# Sherlock.net
KiCad netlist of a schematic drawn in EAGLE
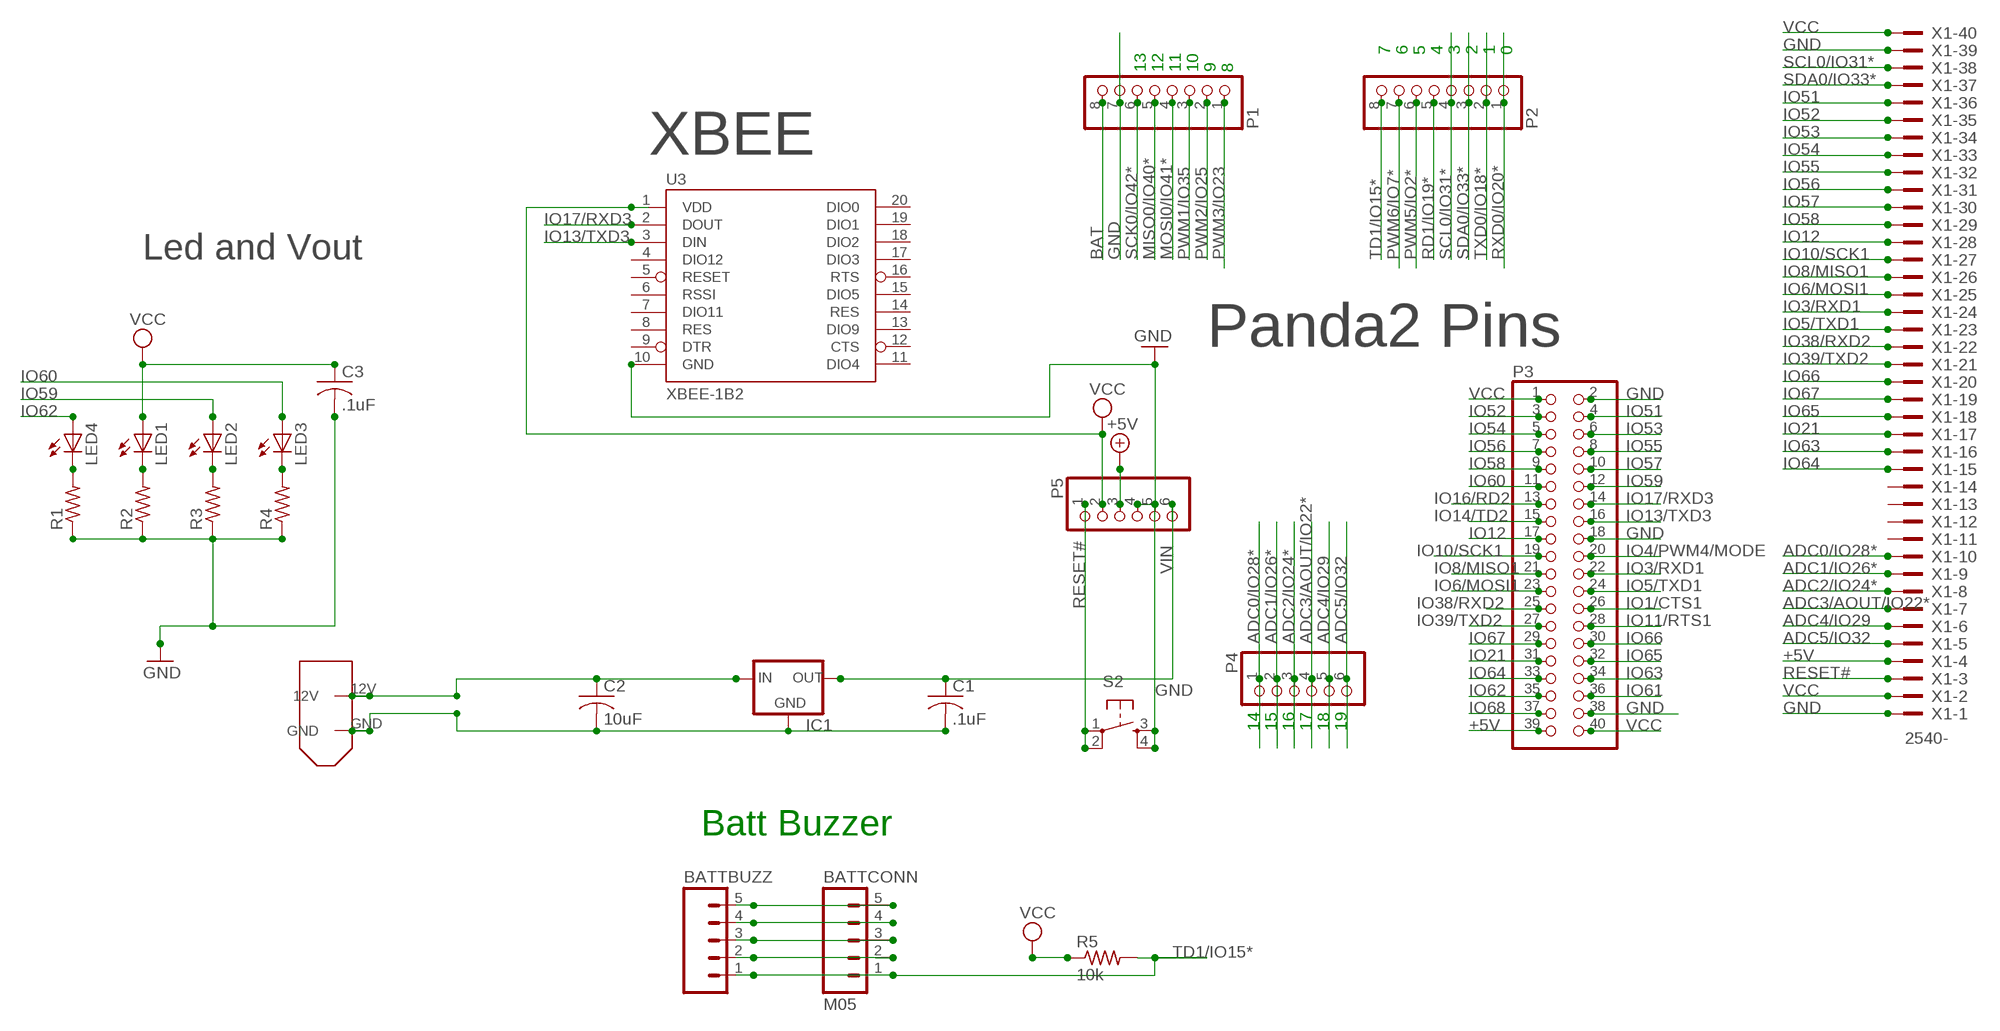
[diagram p0: schematic, sheet 1]

(export (version "E")
  (design (tool "Eeschema 10.0.6"))
  (components
    (comp (ref "BATTBUZZ")
      (value "M05PTH")
      (footprint "eagle-import:1X05")
      (libsource (lib "eagle-import") (part "M05PTH"))
    )
    (comp (ref "BATTCONN")
      (value "M05")
      (footprint "eagle-import:1X05")
      (libsource (lib "eagle-import") (part "M05"))
    )
    (comp (ref "C1")
      (value ".1uF")
      (footprint "eagle-import:C0603")
      (libsource (lib "eagle-import") (part "C-USC0603"))
    )
    (comp (ref "C2")
      (value "10uF")
      (footprint "eagle-import:C0603")
      (libsource (lib "eagle-import") (part "C-USC0603"))
    )
    (comp (ref "C3")
      (value ".1uF")
      (footprint "eagle-import:C0603K")
      (libsource (lib "eagle-import") (part "C-USC0603K"))
    )
    (comp (ref "IC1")
      (value "78XXL")
      (footprint "eagle-import:78XXL")
      (libsource (lib "eagle-import") (part "78XXL"))
    )
    (comp (ref "LED1")
      (value "LED0603")
      (footprint "eagle-import:LED-0603")
      (libsource (lib "eagle-import") (part "LED0603"))
    )
    (comp (ref "LED2")
      (value "LED0603")
      (footprint "eagle-import:LED-0603")
      (libsource (lib "eagle-import") (part "LED0603"))
    )
    (comp (ref "LED3")
      (value "LED0603")
      (footprint "eagle-import:LED-0603")
      (libsource (lib "eagle-import") (part "LED0603"))
    )
    (comp (ref "LED4")
      (value "LED0603")
      (footprint "eagle-import:LED-0603")
      (libsource (lib "eagle-import") (part "LED0603"))
    )
    (comp (ref "P1")
      (value "PINHD-1X08_2.54-S")
      (footprint "eagle-import:1X08-S")
      (libsource (lib "eagle-import") (part "PINHD-1X08_2.54-S"))
    )
    (comp (ref "P2")
      (value "PINHD-1X08_2.54-S")
      (footprint "eagle-import:1X08-S")
      (libsource (lib "eagle-import") (part "PINHD-1X08_2.54-S"))
    )
    (comp (ref "P3")
      (value "PINHD-2X20")
      (footprint "eagle-import:2X20")
      (libsource (lib "eagle-import") (part "PINHD-2X20"))
    )
    (comp (ref "P4")
      (value "PINHD-1X06_2.54-S")
      (footprint "eagle-import:1X06-S")
      (libsource (lib "eagle-import") (part "PINHD-1X06_2.54-S"))
    )
    (comp (ref "P5")
      (value "PINHD-1X06_2.54-S")
      (footprint "eagle-import:1X06-S")
      (libsource (lib "eagle-import") (part "PINHD-1X06_2.54-S"))
    )
    (comp (ref "R1")
      (value "R-US_R0603")
      (footprint "eagle-import:R0603")
      (libsource (lib "eagle-import") (part "R-US_R0603"))
    )
    (comp (ref "R2")
      (value "R-US_R0603")
      (footprint "eagle-import:R0603")
      (libsource (lib "eagle-import") (part "R-US_R0603"))
    )
    (comp (ref "R3")
      (value "R-US_R0603")
      (footprint "eagle-import:R0603")
      (libsource (lib "eagle-import") (part "R-US_R0603"))
    )
    (comp (ref "R4")
      (value "R-US_R0603")
      (footprint "eagle-import:R0603")
      (libsource (lib "eagle-import") (part "R-US_R0603"))
    )
    (comp (ref "R5")
      (value "10k")
      (footprint "eagle-import:R0603")
      (libsource (lib "eagle-import") (part "resistor_R-US_R0603"))
    )
    (comp (ref "S2")
      (value "TAC_SWITCHPTH")
      (footprint "eagle-import:TACTILE-PTH")
      (libsource (lib "eagle-import") (part "TAC_SWITCHPTH"))
    )
    (comp (ref "U$1")
      (value "XT60CONNECTOR")
      (footprint "eagle-import:XT60CONNECTOR")
      (libsource (lib "eagle-import") (part "XT60CONNECTOR"))
    )
    (comp (ref "U3")
      (value "XBEE-1B2")
      (footprint "eagle-import:XBEE-SILK")
      (libsource (lib "eagle-import") (part "XBEE-1B2"))
    )
    (comp (ref "X1")
      (value "2540-")
      (footprint "eagle-import:PAK100_2500-40")
      (fields (field (name "OC_FARNELL") "unknown"))
      (libsource (lib "eagle-import") (part "2540-"))
    )
  )
  (nets
    (net (code "1") (name "+5V") (class "Default")
      (node (ref "P3") (pin "39") (pinfunction "39_39") (pintype "passive"))
      (node (ref "P5") (pin "3") (pinfunction "3_3") (pintype "passive"))
      (node (ref "X1") (pin "4") (pinfunction "KL_4") (pintype "passive"))
    )
    (net (code "2") (name "/ADC0{slash}IO28*") (class "Default")
      (node (ref "P4") (pin "1") (pinfunction "1_1") (pintype "passive"))
      (node (ref "X1") (pin "10") (pinfunction "KL_10") (pintype "passive"))
    )
    (net (code "3") (name "/ADC1{slash}IO26*") (class "Default")
      (node (ref "P4") (pin "2") (pinfunction "2_2") (pintype "passive"))
      (node (ref "X1") (pin "9") (pinfunction "KL_9") (pintype "passive"))
    )
    (net (code "4") (name "/ADC2{slash}IO24*") (class "Default")
      (node (ref "P4") (pin "3") (pinfunction "3_3") (pintype "passive"))
      (node (ref "X1") (pin "8") (pinfunction "KL_8") (pintype "passive"))
    )
    (net (code "5") (name "/ADC3{slash}AOUT{slash}IO22*") (class "Default")
      (node (ref "P4") (pin "4") (pinfunction "4_4") (pintype "passive"))
      (node (ref "X1") (pin "7") (pinfunction "KL_7") (pintype "passive"))
    )
    (net (code "6") (name "/ADC4{slash}IO29") (class "Default")
      (node (ref "P4") (pin "5") (pinfunction "5_5") (pintype "passive"))
      (node (ref "X1") (pin "6") (pinfunction "KL_6") (pintype "passive"))
    )
    (net (code "7") (name "/ADC5{slash}IO32") (class "Default")
      (node (ref "P4") (pin "6") (pinfunction "6_6") (pintype "passive"))
      (node (ref "X1") (pin "5") (pinfunction "KL_5") (pintype "passive"))
    )
    (net (code "8") (name "/BAT") (class "Default")
      (node (ref "P1") (pin "8") (pinfunction "8_8") (pintype "passive"))
    )
    (net (code "9") (name "/IO1{slash}CTS1") (class "Default")
      (node (ref "P3") (pin "26") (pinfunction "26_26") (pintype "passive"))
    )
    (net (code "10") (name "/IO3{slash}RXD1") (class "Default")
      (node (ref "P3") (pin "22") (pinfunction "22_22") (pintype "passive"))
      (node (ref "X1") (pin "24") (pinfunction "KL_24") (pintype "passive"))
    )
    (net (code "11") (name "/IO4{slash}PWM4{slash}MODE") (class "Default")
      (node (ref "P3") (pin "20") (pinfunction "20_20") (pintype "passive"))
    )
    (net (code "12") (name "/IO5{slash}TXD1") (class "Default")
      (node (ref "P3") (pin "24") (pinfunction "24_24") (pintype "passive"))
      (node (ref "X1") (pin "23") (pinfunction "KL_23") (pintype "passive"))
    )
    (net (code "13") (name "/IO6{slash}MOSI1") (class "Default")
      (node (ref "P3") (pin "23") (pinfunction "23_23") (pintype "passive"))
      (node (ref "X1") (pin "25") (pinfunction "KL_25") (pintype "passive"))
    )
    (net (code "14") (name "/IO8{slash}MISO1") (class "Default")
      (node (ref "P3") (pin "21") (pinfunction "21_21") (pintype "passive"))
      (node (ref "X1") (pin "26") (pinfunction "KL_26") (pintype "passive"))
    )
    (net (code "15") (name "/IO10{slash}SCK1") (class "Default")
      (node (ref "P3") (pin "19") (pinfunction "19_19") (pintype "passive"))
      (node (ref "X1") (pin "27") (pinfunction "KL_27") (pintype "passive"))
    )
    (net (code "16") (name "/IO11{slash}RTS1") (class "Default")
      (node (ref "P3") (pin "28") (pinfunction "28_28") (pintype "passive"))
    )
    (net (code "17") (name "/IO12") (class "Default")
      (node (ref "P3") (pin "17") (pinfunction "17_17") (pintype "passive"))
      (node (ref "X1") (pin "28") (pinfunction "KL_28") (pintype "passive"))
    )
    (net (code "18") (name "/IO13{slash}TXD3") (class "Default")
      (node (ref "P3") (pin "16") (pinfunction "16_16") (pintype "passive"))
      (node (ref "U3") (pin "3") (pinfunction "DIN_3") (pintype "input"))
    )
    (net (code "19") (name "/IO14{slash}TD2") (class "Default")
      (node (ref "P3") (pin "15") (pinfunction "15_15") (pintype "passive"))
    )
    (net (code "20") (name "/IO16{slash}RD2") (class "Default")
      (node (ref "P3") (pin "13") (pinfunction "13_13") (pintype "passive"))
    )
    (net (code "21") (name "/IO17{slash}RXD3") (class "Default")
      (node (ref "P3") (pin "14") (pinfunction "14_14") (pintype "passive"))
      (node (ref "U3") (pin "2") (pinfunction "DOUT_2") (pintype "output"))
    )
    (net (code "22") (name "/IO21") (class "Default")
      (node (ref "P3") (pin "31") (pinfunction "31_31") (pintype "passive"))
      (node (ref "X1") (pin "17") (pinfunction "KL_17") (pintype "passive"))
    )
    (net (code "23") (name "/IO38{slash}RXD2") (class "Default")
      (node (ref "P3") (pin "25") (pinfunction "25_25") (pintype "passive"))
      (node (ref "X1") (pin "22") (pinfunction "KL_22") (pintype "passive"))
    )
    (net (code "24") (name "/IO39{slash}TXD2") (class "Default")
      (node (ref "P3") (pin "27") (pinfunction "27_27") (pintype "passive"))
      (node (ref "X1") (pin "21") (pinfunction "KL_21") (pintype "passive"))
    )
    (net (code "25") (name "/IO51") (class "Default")
      (node (ref "P3") (pin "4") (pinfunction "4_4") (pintype "passive"))
      (node (ref "X1") (pin "36") (pinfunction "KL_36") (pintype "passive"))
    )
    (net (code "26") (name "/IO52") (class "Default")
      (node (ref "P3") (pin "3") (pinfunction "3_3") (pintype "passive"))
      (node (ref "X1") (pin "35") (pinfunction "KL_35") (pintype "passive"))
    )
    (net (code "27") (name "/IO53") (class "Default")
      (node (ref "P3") (pin "6") (pinfunction "6_6") (pintype "passive"))
      (node (ref "X1") (pin "34") (pinfunction "KL_34") (pintype "passive"))
    )
    (net (code "28") (name "/IO54") (class "Default")
      (node (ref "P3") (pin "5") (pinfunction "5_5") (pintype "passive"))
      (node (ref "X1") (pin "33") (pinfunction "KL_33") (pintype "passive"))
    )
    (net (code "29") (name "/IO55") (class "Default")
      (node (ref "P3") (pin "8") (pinfunction "8_8") (pintype "passive"))
      (node (ref "X1") (pin "32") (pinfunction "KL_32") (pintype "passive"))
    )
    (net (code "30") (name "/IO56") (class "Default")
      (node (ref "P3") (pin "7") (pinfunction "7_7") (pintype "passive"))
      (node (ref "X1") (pin "31") (pinfunction "KL_31") (pintype "passive"))
    )
    (net (code "31") (name "/IO57") (class "Default")
      (node (ref "P3") (pin "10") (pinfunction "10_10") (pintype "passive"))
      (node (ref "X1") (pin "30") (pinfunction "KL_30") (pintype "passive"))
    )
    (net (code "32") (name "/IO58") (class "Default")
      (node (ref "P3") (pin "9") (pinfunction "9_9") (pintype "passive"))
      (node (ref "X1") (pin "29") (pinfunction "KL_29") (pintype "passive"))
    )
    (net (code "33") (name "/IO59") (class "Default")
      (node (ref "LED2") (pin "A") (pinfunction "A_A") (pintype "passive"))
      (node (ref "P3") (pin "12") (pinfunction "12_12") (pintype "passive"))
    )
    (net (code "34") (name "/IO60") (class "Default")
      (node (ref "LED3") (pin "A") (pinfunction "A_A") (pintype "passive"))
      (node (ref "P3") (pin "11") (pinfunction "11_11") (pintype "passive"))
    )
    (net (code "35") (name "/IO61") (class "Default")
      (node (ref "P3") (pin "36") (pinfunction "36_36") (pintype "passive"))
    )
    (net (code "36") (name "/IO62") (class "Default")
      (node (ref "LED4") (pin "A") (pinfunction "A_A") (pintype "passive"))
      (node (ref "P3") (pin "35") (pinfunction "35_35") (pintype "passive"))
    )
    (net (code "37") (name "/IO63") (class "Default")
      (node (ref "P3") (pin "34") (pinfunction "34_34") (pintype "passive"))
      (node (ref "X1") (pin "16") (pinfunction "KL_16") (pintype "passive"))
    )
    (net (code "38") (name "/IO64") (class "Default")
      (node (ref "P3") (pin "33") (pinfunction "33_33") (pintype "passive"))
      (node (ref "X1") (pin "15") (pinfunction "KL_15") (pintype "passive"))
    )
    (net (code "39") (name "/IO65") (class "Default")
      (node (ref "P3") (pin "32") (pinfunction "32_32") (pintype "passive"))
      (node (ref "X1") (pin "18") (pinfunction "KL_18") (pintype "passive"))
    )
    (net (code "40") (name "/IO66") (class "Default")
      (node (ref "P3") (pin "30") (pinfunction "30_30") (pintype "passive"))
      (node (ref "X1") (pin "20") (pinfunction "KL_20") (pintype "passive"))
    )
    (net (code "41") (name "/IO67") (class "Default")
      (node (ref "P3") (pin "29") (pinfunction "29_29") (pintype "passive"))
      (node (ref "X1") (pin "19") (pinfunction "KL_19") (pintype "passive"))
    )
    (net (code "42") (name "/IO68") (class "Default")
      (node (ref "P3") (pin "37") (pinfunction "37_37") (pintype "passive"))
    )
    (net (code "43") (name "/MISO0{slash}IO40*") (class "Default")
      (node (ref "P1") (pin "5") (pinfunction "5_5") (pintype "passive"))
    )
    (net (code "44") (name "/MOSI0{slash}IO41*") (class "Default")
      (node (ref "P1") (pin "4") (pinfunction "4_4") (pintype "passive"))
    )
    (net (code "45") (name "/PWM1{slash}IO35") (class "Default")
      (node (ref "P1") (pin "3") (pinfunction "3_3") (pintype "passive"))
    )
    (net (code "46") (name "/PWM2{slash}IO25") (class "Default")
      (node (ref "P1") (pin "2") (pinfunction "2_2") (pintype "passive"))
    )
    (net (code "47") (name "/PWM3{slash}IO23") (class "Default")
      (node (ref "P1") (pin "1") (pinfunction "1_1") (pintype "passive"))
    )
    (net (code "48") (name "/PWM5{slash}IO2*") (class "Default")
      (node (ref "P2") (pin "6") (pinfunction "6_6") (pintype "passive"))
    )
    (net (code "49") (name "/PWM6{slash}IO7*") (class "Default")
      (node (ref "P2") (pin "7") (pinfunction "7_7") (pintype "passive"))
    )
    (net (code "50") (name "/RD1{slash}IO19*") (class "Default")
      (node (ref "P2") (pin "5") (pinfunction "5_5") (pintype "passive"))
    )
    (net (code "51") (name "/RESET#") (class "Default")
      (node (ref "P5") (pin "1") (pinfunction "1_1") (pintype "passive"))
      (node (ref "S2") (pin "1") (pinfunction "1_1") (pintype "passive"))
      (node (ref "S2") (pin "2") (pinfunction "2_2") (pintype "passive"))
      (node (ref "X1") (pin "3") (pinfunction "KL_3") (pintype "passive"))
    )
    (net (code "52") (name "/RXD0{slash}IO20*") (class "Default")
      (node (ref "P2") (pin "1") (pinfunction "1_1") (pintype "passive"))
    )
    (net (code "53") (name "/SCK0{slash}IO42*") (class "Default")
      (node (ref "P1") (pin "6") (pinfunction "6_6") (pintype "passive"))
    )
    (net (code "54") (name "/SCL0{slash}IO31*") (class "Default")
      (node (ref "P2") (pin "4") (pinfunction "4_4") (pintype "passive"))
      (node (ref "X1") (pin "38") (pinfunction "KL_38") (pintype "passive"))
    )
    (net (code "55") (name "/SDA0{slash}IO33*") (class "Default")
      (node (ref "P2") (pin "3") (pinfunction "3_3") (pintype "passive"))
      (node (ref "X1") (pin "37") (pinfunction "KL_37") (pintype "passive"))
    )
    (net (code "56") (name "/TD1{slash}IO15*") (class "Default")
      (node (ref "BATTBUZZ") (pin "1") (pinfunction "1_1") (pintype "passive"))
      (node (ref "BATTCONN") (pin "1") (pinfunction "1_1") (pintype "passive"))
      (node (ref "P2") (pin "8") (pinfunction "8_8") (pintype "passive"))
      (node (ref "R5") (pin "2") (pinfunction "2_2") (pintype "passive"))
    )
    (net (code "57") (name "/TXD0{slash}IO18*") (class "Default")
      (node (ref "P2") (pin "2") (pinfunction "2_2") (pintype "passive"))
    )
    (net (code "58") (name "/VIN") (class "Default")
      (node (ref "C1") (pin "1") (pinfunction "1_1") (pintype "passive"))
      (node (ref "IC1") (pin "OUT") (pinfunction "OUT_OUT") (pintype "passive"))
      (node (ref "P5") (pin "6") (pinfunction "6_6") (pintype "passive"))
    )
    (net (code "59") (name "GND") (class "Default")
      (node (ref "C1") (pin "2") (pinfunction "2_2") (pintype "passive"))
      (node (ref "C2") (pin "2") (pinfunction "2_2") (pintype "passive"))
      (node (ref "C3") (pin "2") (pinfunction "2_2") (pintype "passive"))
      (node (ref "IC1") (pin "GND") (pinfunction "GND_GND") (pintype "input"))
      (node (ref "P1") (pin "7") (pinfunction "7_7") (pintype "passive"))
      (node (ref "P3") (pin "18") (pinfunction "18_18") (pintype "passive"))
      (node (ref "P3") (pin "2") (pinfunction "2_2") (pintype "passive"))
      (node (ref "P3") (pin "38") (pinfunction "38_38") (pintype "passive"))
      (node (ref "P5") (pin "4") (pinfunction "4_4") (pintype "passive"))
      (node (ref "P5") (pin "5") (pinfunction "5_5") (pintype "passive"))
      (node (ref "R1") (pin "1") (pinfunction "1_1") (pintype "passive"))
      (node (ref "R2") (pin "1") (pinfunction "1_1") (pintype "passive"))
      (node (ref "R3") (pin "1") (pinfunction "1_1") (pintype "passive"))
      (node (ref "R4") (pin "1") (pinfunction "1_1") (pintype "passive"))
      (node (ref "S2") (pin "3") (pinfunction "3_3") (pintype "passive"))
      (node (ref "S2") (pin "4") (pinfunction "4_4") (pintype "passive"))
      (node (ref "U$1") (pin "GND") (pinfunction "GND_GND") (pintype "bidirectional"))
      (node (ref "U3") (pin "10") (pinfunction "GND_10") (pintype "power_in"))
      (node (ref "X1") (pin "1") (pinfunction "KL_1") (pintype "passive"))
      (node (ref "X1") (pin "39") (pinfunction "KL_39") (pintype "passive"))
    )
    (net (code "60") (name "Net-(BATTBUZZ-Pad2)") (class "Default")
      (node (ref "BATTBUZZ") (pin "2") (pinfunction "2_2") (pintype "passive"))
      (node (ref "BATTCONN") (pin "2") (pinfunction "2_2") (pintype "passive"))
    )
    (net (code "61") (name "Net-(BATTBUZZ-Pad3)") (class "Default")
      (node (ref "BATTBUZZ") (pin "3") (pinfunction "3_3") (pintype "passive"))
      (node (ref "BATTCONN") (pin "3") (pinfunction "3_3") (pintype "passive"))
    )
    (net (code "62") (name "Net-(BATTBUZZ-Pad4)") (class "Default")
      (node (ref "BATTBUZZ") (pin "4") (pinfunction "4_4") (pintype "passive"))
      (node (ref "BATTCONN") (pin "4") (pinfunction "4_4") (pintype "passive"))
    )
    (net (code "63") (name "Net-(BATTBUZZ-Pad5)") (class "Default")
      (node (ref "BATTBUZZ") (pin "5") (pinfunction "5_5") (pintype "passive"))
      (node (ref "BATTCONN") (pin "5") (pinfunction "5_5") (pintype "passive"))
    )
    (net (code "64") (name "Net-(C2-Pad1)") (class "Default")
      (node (ref "C2") (pin "1") (pinfunction "1_1") (pintype "passive"))
      (node (ref "IC1") (pin "IN") (pinfunction "IN_IN") (pintype "input"))
      (node (ref "U$1") (pin "12V") (pinfunction "12V_12V") (pintype "bidirectional"))
    )
    (net (code "65") (name "Net-(LED1-PadC)") (class "Default")
      (node (ref "LED1") (pin "C") (pinfunction "C_C") (pintype "passive"))
      (node (ref "R2") (pin "2") (pinfunction "2_2") (pintype "passive"))
    )
    (net (code "66") (name "Net-(LED2-PadC)") (class "Default")
      (node (ref "LED2") (pin "C") (pinfunction "C_C") (pintype "passive"))
      (node (ref "R3") (pin "2") (pinfunction "2_2") (pintype "passive"))
    )
    (net (code "67") (name "Net-(LED3-PadC)") (class "Default")
      (node (ref "LED3") (pin "C") (pinfunction "C_C") (pintype "passive"))
      (node (ref "R4") (pin "2") (pinfunction "2_2") (pintype "passive"))
    )
    (net (code "68") (name "Net-(LED4-PadC)") (class "Default")
      (node (ref "LED4") (pin "C") (pinfunction "C_C") (pintype "passive"))
      (node (ref "R1") (pin "2") (pinfunction "2_2") (pintype "passive"))
    )
    (net (code "69") (name "VCC") (class "Default")
      (node (ref "C3") (pin "1") (pinfunction "1_1") (pintype "passive"))
      (node (ref "LED1") (pin "A") (pinfunction "A_A") (pintype "passive"))
      (node (ref "P3") (pin "1") (pinfunction "1_1") (pintype "passive"))
      (node (ref "P3") (pin "40") (pinfunction "40_40") (pintype "passive"))
      (node (ref "P5") (pin "2") (pinfunction "2_2") (pintype "passive"))
      (node (ref "R5") (pin "1") (pinfunction "1_1") (pintype "passive"))
      (node (ref "U3") (pin "1") (pinfunction "VDD_1") (pintype "power_in"))
      (node (ref "X1") (pin "2") (pinfunction "KL_2") (pintype "passive"))
      (node (ref "X1") (pin "40") (pinfunction "KL_40") (pintype "passive"))
    )
    (net (code "70") (name "unconnected-(U3-CTS-Pad12)") (class "Default")
      (node (ref "U3") (pin "12") (pinfunction "CTS_12") (pintype "output"))
    )
    (net (code "71") (name "unconnected-(U3-DIO0-Pad20)") (class "Default")
      (node (ref "U3") (pin "20") (pinfunction "DIO0_20") (pintype "bidirectional"))
    )
    (net (code "72") (name "unconnected-(U3-DIO1-Pad19)") (class "Default")
      (node (ref "U3") (pin "19") (pinfunction "DIO1_19") (pintype "bidirectional"))
    )
    (net (code "73") (name "unconnected-(U3-DIO2-Pad18)") (class "Default")
      (node (ref "U3") (pin "18") (pinfunction "DIO2_18") (pintype "bidirectional"))
    )
    (net (code "74") (name "unconnected-(U3-DIO3-Pad17)") (class "Default")
      (node (ref "U3") (pin "17") (pinfunction "DIO3_17") (pintype "bidirectional"))
    )
    (net (code "75") (name "unconnected-(U3-DIO4-Pad11)") (class "Default")
      (node (ref "U3") (pin "11") (pinfunction "DIO4_11") (pintype "bidirectional"))
    )
    (net (code "76") (name "unconnected-(U3-DIO5-Pad15)") (class "Default")
      (node (ref "U3") (pin "15") (pinfunction "DIO5_15") (pintype "bidirectional"))
    )
    (net (code "77") (name "unconnected-(U3-DIO9-Pad13)") (class "Default")
      (node (ref "U3") (pin "13") (pinfunction "DIO9_13") (pintype "bidirectional"))
    )
    (net (code "78") (name "unconnected-(U3-DIO11-Pad7)") (class "Default")
      (node (ref "U3") (pin "7") (pinfunction "DIO11_7") (pintype "bidirectional"))
    )
    (net (code "79") (name "unconnected-(U3-DIO12-Pad4)") (class "Default")
      (node (ref "U3") (pin "4") (pinfunction "DIO12_4") (pintype "bidirectional"))
    )
    (net (code "80") (name "unconnected-(U3-DTR-Pad9)") (class "Default")
      (node (ref "U3") (pin "9") (pinfunction "DTR_9") (pintype "bidirectional"))
    )
    (net (code "81") (name "unconnected-(U3-RES-Pad8)") (class "Default")
      (node (ref "U3") (pin "8") (pinfunction "RES_8") (pintype "bidirectional"))
    )
    (net (code "82") (name "unconnected-(U3-RES-Pad14)") (class "Default")
      (node (ref "U3") (pin "14") (pinfunction "RES_14") (pintype "bidirectional"))
    )
    (net (code "83") (name "unconnected-(U3-RESET-Pad5)") (class "Default")
      (node (ref "U3") (pin "5") (pinfunction "RESET_5") (pintype "input"))
    )
    (net (code "84") (name "unconnected-(U3-RSSI-Pad6)") (class "Default")
      (node (ref "U3") (pin "6") (pinfunction "RSSI_6") (pintype "bidirectional"))
    )
    (net (code "85") (name "unconnected-(U3-RTS-Pad16)") (class "Default")
      (node (ref "U3") (pin "16") (pinfunction "RTS_16") (pintype "input"))
    )
    (net (code "86") (name "unconnected-(X1C-KL-Pad11)") (class "Default")
      (node (ref "X1") (pin "11") (pinfunction "KL_11") (pintype "passive"))
    )
    (net (code "87") (name "unconnected-(X1D-KL-Pad12)") (class "Default")
      (node (ref "X1") (pin "12") (pinfunction "KL_12") (pintype "passive"))
    )
    (net (code "88") (name "unconnected-(X1E-KL-Pad13)") (class "Default")
      (node (ref "X1") (pin "13") (pinfunction "KL_13") (pintype "passive"))
    )
    (net (code "89") (name "unconnected-(X1F-KL-Pad14)") (class "Default")
      (node (ref "X1") (pin "14") (pinfunction "KL_14") (pintype "passive"))
    )
  )
)
